# FPGA_Power_Mannager.net
KiCad netlist of a schematic drawn in Altium Designer
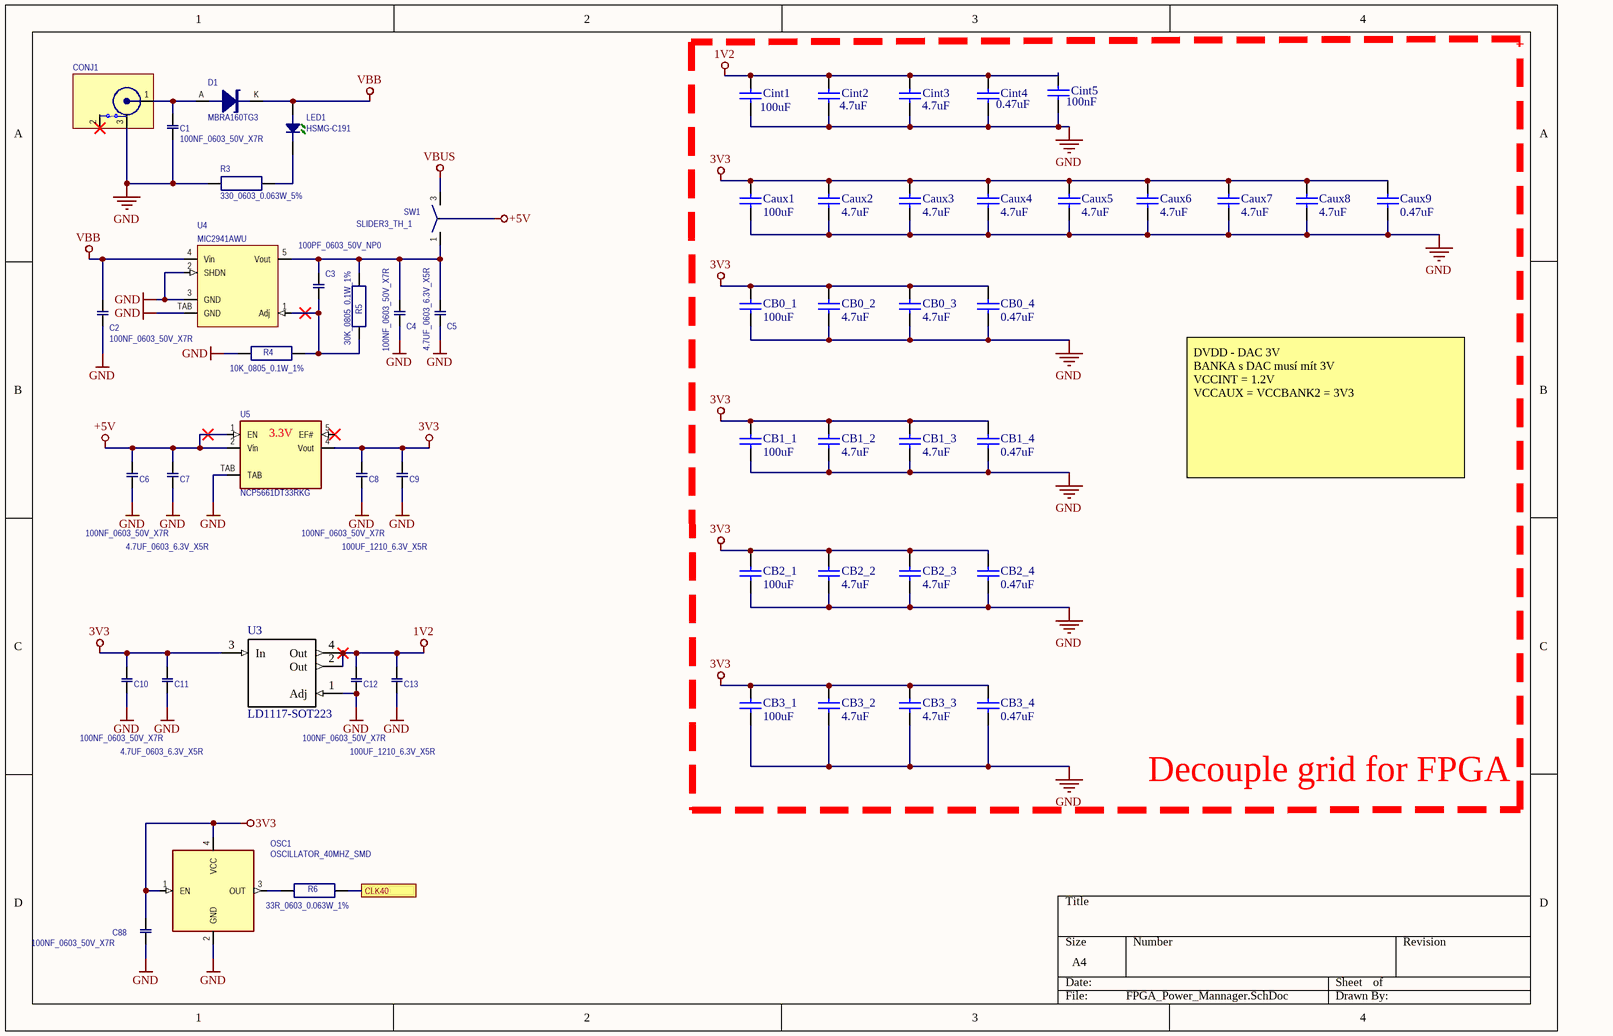
[diagram p0: FPGA_Power_Mannager.SchDoc]

(export (version "E")
  (design (tool "Eeschema 10.0.6"))
  (components
    (comp (ref "C1")
      (value "100NF_0603_50V_X7R")
      (footprint "CAP0603")
      (description "128-8255    Capacitor MLC-X7R_0603_100NF_10%_50V; C0603C104K5RAC; KEMET; RoHS=Yes")
      (libsource (lib "*") (part "100NF_0603_50V_X7R"))
    )
    (comp (ref "C2")
      (value "100NF_0603_50V_X7R")
      (footprint "CAP0603")
      (description "128-8255    Capacitor MLC-X7R_0603_100NF_10%_50V; C0603C104K5RAC; KEMET; RoHS=Yes")
      (libsource (lib "*") (part "100NF_0603_50V_X7R"))
    )
    (comp (ref "C3")
      (value "100PF_0603_50V_NP0")
      (footprint "CAP0603")
      (description "141-4603    Capacitor MLC-NPO_0603_100PF_5%_50V; C0603C101J5GAC; KEMET; RoHS=Yes")
      (libsource (lib "*") (part "100PF_0603_50V_NP0"))
    )
    (comp (ref "C4")
      (value "100NF_0603_50V_X7R")
      (footprint "CAP0603")
      (description "128-8255    Capacitor MLC-X7R_0603_100NF_10%_50V; C0603C104K5RAC; KEMET; RoHS=Yes")
      (libsource (lib "*") (part "100NF_0603_50V_X7R"))
    )
    (comp (ref "C5")
      (value "4.7UF_0603_6.3V_X5R")
      (footprint "CAP0603")
      (description "940-2110    Capacitor MLC-X5R_0603_4.7uF_10%_6.3V; 225520613672; PHYCOMP; RoHS=Yes")
      (libsource (lib "*") (part "4.7UF_0603_6.3V_X5R"))
    )
    (comp (ref "C6")
      (value "100NF_0603_50V_X7R")
      (footprint "CAP0603")
      (description "128-8255    Capacitor MLC-X7R_0603_100NF_10%_50V; C0603C104K5RAC; KEMET; RoHS=Yes")
      (libsource (lib "*") (part "100NF_0603_50V_X7R"))
    )
    (comp (ref "C7")
      (value "4.7UF_0603_6.3V_X5R")
      (footprint "CAP0603")
      (description "940-2110    Capacitor MLC-X5R_0603_4.7uF_10%_6.3V; 225520613672; PHYCOMP; RoHS=Yes")
      (libsource (lib "*") (part "4.7UF_0603_6.3V_X5R"))
    )
    (comp (ref "C8")
      (value "100NF_0603_50V_X7R")
      (footprint "CAP0603")
      (description "128-8255    Capacitor MLC-X7R_0603_100NF_10%_50V; C0603C104K5RAC; KEMET; RoHS=Yes")
      (libsource (lib "*") (part "100NF_0603_50V_X7R"))
    )
    (comp (ref "C9")
      (value "100UF_1210_6.3V_X5R")
      (footprint "CAP1210")
      (description "182-8817    Capacitor CML 100uF_1210_6.3V_X5R_20%; GRM32ER60J107ME20L; MURATA; RoHS=Yes")
      (libsource (lib "*") (part "100UF_1210_6.3V_X5R"))
    )
    (comp (ref "C10")
      (value "100NF_0603_50V_X7R")
      (footprint "CAP0603")
      (description "128-8255    Capacitor MLC-X7R_0603_100NF_10%_50V; C0603C104K5RAC; KEMET; RoHS=Yes")
      (libsource (lib "*") (part "100NF_0603_50V_X7R"))
    )
    (comp (ref "C11")
      (value "4.7UF_0603_6.3V_X5R")
      (footprint "CAP0603")
      (description "940-2110    Capacitor MLC-X5R_0603_4.7uF_10%_6.3V; 225520613672; PHYCOMP; RoHS=Yes")
      (libsource (lib "*") (part "4.7UF_0603_6.3V_X5R"))
    )
    (comp (ref "C12")
      (value "100NF_0603_50V_X7R")
      (footprint "CAP0603")
      (description "128-8255    Capacitor MLC-X7R_0603_100NF_10%_50V; C0603C104K5RAC; KEMET; RoHS=Yes")
      (libsource (lib "*") (part "100NF_0603_50V_X7R"))
    )
    (comp (ref "C13")
      (value "100UF_1210_6.3V_X5R")
      (footprint "CAP1210")
      (description "182-8817    Capacitor CML 100uF_1210_6.3V_X5R_20%; GRM32ER60J107ME20L; MURATA; RoHS=Yes")
      (libsource (lib "*") (part "100UF_1210_6.3V_X5R"))
    )
    (comp (ref "C88")
      (value "100NF_0603_50V_X7R")
      (footprint "CAP0603")
      (description "128-8255    Capacitor MLC-X7R_0603_100NF_10%_50V; C0603C104K5RAC; KEMET; RoHS=Yes")
      (libsource (lib "*") (part "100NF_0603_50V_X7R"))
    )
    (comp (ref "Caux1")
      (value "100uF")
      (footprint "C1206")
      (description "Capacitor (Semiconductor SIM Model)")
      (fields (field (name "Comment") "100UF") (field (name "PUBLISHER") "Altium Limited"))
      (libsource (lib "Miscellaneous Devices") (part "Cap Semi"))
    )
    (comp (ref "Caux2")
      (value "4.7uF")
      (footprint "1608[0603]")
      (description "Capacitor (Semiconductor SIM Model)")
      (fields (field (name "Comment") "4.7UF") (field (name "PUBLISHER") "Altium Limited"))
      (libsource (lib "Miscellaneous Devices") (part "Cap Semi"))
    )
    (comp (ref "Caux3")
      (value "4.7uF")
      (footprint "1608[0603]")
      (description "Capacitor (Semiconductor SIM Model)")
      (fields (field (name "Comment") "4.7UF") (field (name "PUBLISHER") "Altium Limited"))
      (libsource (lib "Miscellaneous Devices") (part "Cap Semi"))
    )
    (comp (ref "Caux4")
      (value "4.7uF")
      (footprint "1608[0603]")
      (description "Capacitor (Semiconductor SIM Model)")
      (fields (field (name "Comment") "4.7UF") (field (name "PUBLISHER") "Altium Limited"))
      (libsource (lib "Miscellaneous Devices") (part "Cap Semi"))
    )
    (comp (ref "Caux5")
      (value "4.7uF")
      (footprint "1608[0603]")
      (description "Capacitor (Semiconductor SIM Model)")
      (fields (field (name "Comment") "4.7UF") (field (name "PUBLISHER") "Altium Limited"))
      (libsource (lib "Miscellaneous Devices") (part "Cap Semi"))
    )
    (comp (ref "Caux6")
      (value "4.7uF")
      (footprint "1608[0603]")
      (description "Capacitor (Semiconductor SIM Model)")
      (fields (field (name "Comment") "4.7UF") (field (name "PUBLISHER") "Altium Limited"))
      (libsource (lib "Miscellaneous Devices") (part "Cap Semi"))
    )
    (comp (ref "Caux7")
      (value "4.7uF")
      (footprint "1608[0603]")
      (description "Capacitor (Semiconductor SIM Model)")
      (fields (field (name "Comment") "4.7UF") (field (name "PUBLISHER") "Altium Limited"))
      (libsource (lib "Miscellaneous Devices") (part "Cap Semi"))
    )
    (comp (ref "Caux8")
      (value "4.7uF")
      (footprint "1608[0603]")
      (description "Capacitor (Semiconductor SIM Model)")
      (fields (field (name "Comment") "4.7UF") (field (name "PUBLISHER") "Altium Limited"))
      (libsource (lib "Miscellaneous Devices") (part "Cap Semi"))
    )
    (comp (ref "Caux9")
      (value "0.47uF")
      (footprint "1608[0603]")
      (description "Capacitor (Semiconductor SIM Model)")
      (fields (field (name "Comment") "470nF") (field (name "PUBLISHER") "Altium Limited"))
      (libsource (lib "Miscellaneous Devices") (part "Cap Semi"))
    )
    (comp (ref "CB0_1")
      (value "100uF")
      (footprint "C1206")
      (description "Capacitor (Semiconductor SIM Model)")
      (fields (field (name "Comment") "100UF") (field (name "PUBLISHER") "Altium Limited"))
      (libsource (lib "Miscellaneous Devices") (part "Cap Semi"))
    )
    (comp (ref "CB0_2")
      (value "4.7uF")
      (footprint "1608[0603]")
      (description "Capacitor (Semiconductor SIM Model)")
      (fields (field (name "Comment") "4.7UF") (field (name "PUBLISHER") "Altium Limited"))
      (libsource (lib "Miscellaneous Devices") (part "Cap Semi"))
    )
    (comp (ref "CB0_3")
      (value "4.7uF")
      (footprint "1608[0603]")
      (description "Capacitor (Semiconductor SIM Model)")
      (fields (field (name "Comment") "4.7UF") (field (name "PUBLISHER") "Altium Limited"))
      (libsource (lib "Miscellaneous Devices") (part "Cap Semi"))
    )
    (comp (ref "CB0_4")
      (value "0.47uF")
      (footprint "1608[0603]")
      (description "Capacitor (Semiconductor SIM Model)")
      (fields (field (name "Comment") "470nF") (field (name "PUBLISHER") "Altium Limited"))
      (libsource (lib "Miscellaneous Devices") (part "Cap Semi"))
    )
    (comp (ref "CB1_1")
      (value "100uF")
      (footprint "C1206")
      (description "Capacitor (Semiconductor SIM Model)")
      (fields (field (name "Comment") "100UF") (field (name "PUBLISHER") "Altium Limited"))
      (libsource (lib "Miscellaneous Devices") (part "Cap Semi"))
    )
    (comp (ref "CB1_2")
      (value "4.7uF")
      (footprint "1608[0603]")
      (description "Capacitor (Semiconductor SIM Model)")
      (fields (field (name "Comment") "4.7UF") (field (name "PUBLISHER") "Altium Limited"))
      (libsource (lib "Miscellaneous Devices") (part "Cap Semi"))
    )
    (comp (ref "CB1_3")
      (value "4.7uF")
      (footprint "1608[0603]")
      (description "Capacitor (Semiconductor SIM Model)")
      (fields (field (name "Comment") "4.7UF") (field (name "PUBLISHER") "Altium Limited"))
      (libsource (lib "Miscellaneous Devices") (part "Cap Semi"))
    )
    (comp (ref "CB1_4")
      (value "0.47uF")
      (footprint "1608[0603]")
      (description "Capacitor (Semiconductor SIM Model)")
      (fields (field (name "Comment") "470nF") (field (name "PUBLISHER") "Altium Limited"))
      (libsource (lib "Miscellaneous Devices") (part "Cap Semi"))
    )
    (comp (ref "CB2_1")
      (value "100uF")
      (footprint "C1206")
      (description "Capacitor (Semiconductor SIM Model)")
      (fields (field (name "Comment") "100UF") (field (name "PUBLISHER") "Altium Limited"))
      (libsource (lib "Miscellaneous Devices") (part "Cap Semi"))
    )
    (comp (ref "CB2_2")
      (value "4.7uF")
      (footprint "1608[0603]")
      (description "Capacitor (Semiconductor SIM Model)")
      (fields (field (name "Comment") "4.7UF") (field (name "PUBLISHER") "Altium Limited"))
      (libsource (lib "Miscellaneous Devices") (part "Cap Semi"))
    )
    (comp (ref "CB2_3")
      (value "4.7uF")
      (footprint "1608[0603]")
      (description "Capacitor (Semiconductor SIM Model)")
      (fields (field (name "Comment") "4.7UF") (field (name "PUBLISHER") "Altium Limited"))
      (libsource (lib "Miscellaneous Devices") (part "Cap Semi"))
    )
    (comp (ref "CB2_4")
      (value "0.47uF")
      (footprint "1608[0603]")
      (description "Capacitor (Semiconductor SIM Model)")
      (fields (field (name "Comment") "470nF") (field (name "PUBLISHER") "Altium Limited"))
      (libsource (lib "Miscellaneous Devices") (part "Cap Semi"))
    )
    (comp (ref "CB3_1")
      (value "100uF")
      (footprint "C1206")
      (description "Capacitor (Semiconductor SIM Model)")
      (fields (field (name "Comment") "100UF") (field (name "PUBLISHER") "Altium Limited"))
      (libsource (lib "Miscellaneous Devices") (part "Cap Semi"))
    )
    (comp (ref "CB3_2")
      (value "4.7uF")
      (footprint "1608[0603]")
      (description "Capacitor (Semiconductor SIM Model)")
      (fields (field (name "Comment") "4.7UF") (field (name "PUBLISHER") "Altium Limited"))
      (libsource (lib "Miscellaneous Devices") (part "Cap Semi"))
    )
    (comp (ref "CB3_3")
      (value "4.7uF")
      (footprint "1608[0603]")
      (description "Capacitor (Semiconductor SIM Model)")
      (fields (field (name "Comment") "4.7UF") (field (name "PUBLISHER") "Altium Limited"))
      (libsource (lib "Miscellaneous Devices") (part "Cap Semi"))
    )
    (comp (ref "CB3_4")
      (value "0.47uF")
      (footprint "1608[0603]")
      (description "Capacitor (Semiconductor SIM Model)")
      (fields (field (name "Comment") "470nF") (field (name "PUBLISHER") "Altium Limited"))
      (libsource (lib "Miscellaneous Devices") (part "Cap Semi"))
    )
    (comp (ref "Cint1")
      (value "100uF")
      (footprint "C1206")
      (description "Capacitor (Semiconductor SIM Model)")
      (fields (field (name "Comment") "100UF") (field (name "PUBLISHER") "Altium Limited"))
      (libsource (lib "Miscellaneous Devices") (part "Cap Semi"))
    )
    (comp (ref "Cint2")
      (value "4.7uF")
      (footprint "1608[0603]")
      (description "Capacitor (Semiconductor SIM Model)")
      (fields (field (name "Comment") "4.7UF") (field (name "PUBLISHER") "Altium Limited"))
      (libsource (lib "Miscellaneous Devices") (part "Cap Semi"))
    )
    (comp (ref "Cint3")
      (value "4.7uF")
      (footprint "1608[0603]")
      (description "Capacitor (Semiconductor SIM Model)")
      (fields (field (name "Comment") "4.7UF") (field (name "PUBLISHER") "Altium Limited"))
      (libsource (lib "Miscellaneous Devices") (part "Cap Semi"))
    )
    (comp (ref "Cint4")
      (value "0.47uF")
      (footprint "1608[0603]")
      (description "Capacitor (Semiconductor SIM Model)")
      (fields (field (name "Comment") "470nF") (field (name "PUBLISHER") "Altium Limited"))
      (libsource (lib "Miscellaneous Devices") (part "Cap Semi"))
    )
    (comp (ref "Cint5")
      (value "100nF")
      (footprint "1608[0603]")
      (description "Capacitor (Semiconductor SIM Model)")
      (fields (field (name "PUBLISHER") "Altium Limited"))
      (libsource (lib "Miscellaneous Devices") (part "Cap Semi"))
    )
    (comp (ref "CONJ1")
      (value "CON_POWER_DC10A_CLIFF")
      (footprint "CON_POWER_DC10A_CLIFF")
      (libsource (lib "ONEMULA_V2") (part "CON_POWER_DC10A_CLIFF"))
    )
    (comp (ref "D1")
      (value "MBRA160TG3")
      (footprint "SMA_KA")
      (description "143-1076    DIODE SCHOTTKY 60V/1A; MBRA160TG3; SMA; ONSEMI; RoHS=Yes")
      (libsource (lib "ONEMULA_V2") (part "MBRA160TG3"))
    )
    (comp (ref "LED1")
      (value "HSMG-C191")
      (footprint "D0603")
      (description "855-4617    LED DIODE GREEN 20mA, 0603; HSMG-C191; AVAGO TECHNOLOGIES; RoHS=Yes")
      (libsource (lib "ONEMULA_V2") (part "HSMG-C191"))
    )
    (comp (ref "OSC1")
      (value "OSCILLATOR_40MHZ_SMD")
      (footprint "CFPS-73")
      (libsource (lib "ONEMULA_V1_ALLPATCHES") (part "OSCILLATOR_40MHZ_SMD"))
    )
    (comp (ref "R3")
      (value "330_0603_0.063W_5%")
      (footprint "R0603")
      (description "923-3385    RESISTOR MF_0603_1.0KR_0.063W_5%_50V; 232270260102; PHYCOMP; RoHS=Yes")
      (libsource (lib "ONEMULA_V2") (part "1.0K_0603_0.063W_5%"))
    )
    (comp (ref "R4")
      (value "10K_0805_0.1W_1%")
      (footprint "R0805")
      (libsource (lib "*") (part "10K_0805_0.1W_1%"))
    )
    (comp (ref "R5")
      (value "30K_0805_0.1W_1%")
      (footprint "R0805")
      (libsource (lib "*") (part "30K_0805_0.1W_1%"))
    )
    (comp (ref "R6")
      (value "33R_0603_0.063W_1%")
      (footprint "R0603")
      (description "933-1050    RESISTOR MF_0603_33R_0.063W_1%_50V; MC_0.063W_0603_1%_33R; MULTICOMP; RoHS=Yes")
      (libsource (lib "*") (part "33R_0603_0.063W_1%"))
    )
    (comp (ref "SW1")
      (value "SLIDER3_TH_1")
      (footprint "X3APH-SLIDER")
      (description "674-345     SWITCH SLIDE SPDT VERT; 09-03290-01; EAO; RoHS=Yes")
      (libsource (lib "*") (part "SLIDER3_TH_1"))
    )
    (comp (ref "U3")
      (value "LD1117-SOT223")
      (footprint "SOT223")
      (libsource (lib "vh_altium_library") (part "LD1117-SOT223"))
    )
    (comp (ref "U4")
      (value "MIC2941AWU")
      (footprint "TO263_5")
      (description "155-6739    VOLTAGE REGULATOR, ADJ/1,5A, MIC2941AWU; MICREL; RoHS=Yes")
      (libsource (lib "*") (part "MIC2941AWU"))
    )
    (comp (ref "U5")
      (value "NCP5661DT33RKG")
      (footprint "DPAK5")
      (description "ONSEMI      VOLTAGE REGULATOR NCP5661DT33RKG, LINEAR, LDO, 3.3V/1A, DPAK5; ONSEMI; RoHS=Yes")
      (libsource (lib "ONEMULA_V1_ALLPATCHES") (part "NCP5661DT33RKG"))
    )
  )
  (nets
    (net (code "1") (name "+5V") (class "Default")
      (node (ref "C6") (pin "1") (pinfunction "1_1") (pintype "passive"))
      (node (ref "C7") (pin "1") (pinfunction "1_1") (pintype "passive"))
      (node (ref "SW1") (pin "2") (pinfunction "2_2") (pintype "passive"))
      (node (ref "U5") (pin "1") (pinfunction "EN_1") (pintype "input"))
      (node (ref "U5") (pin "2") (pinfunction "Vin_2") (pintype "power_in"))
    )
    (net (code "2") (name "/CLK40") (class "Default")
      (node (ref "R6") (pin "2") (pinfunction "2_2") (pintype "passive"))
    )
    (net (code "3") (name "1V2") (class "Default")
      (node (ref "C12") (pin "1") (pinfunction "1_1") (pintype "passive"))
      (node (ref "C13") (pin "1") (pinfunction "1_1") (pintype "passive"))
      (node (ref "Cint1") (pin "2") (pinfunction "2_2") (pintype "passive"))
      (node (ref "Cint2") (pin "2") (pinfunction "2_2") (pintype "passive"))
      (node (ref "Cint3") (pin "2") (pinfunction "2_2") (pintype "passive"))
      (node (ref "Cint4") (pin "2") (pinfunction "2_2") (pintype "passive"))
      (node (ref "Cint5") (pin "2") (pinfunction "2_2") (pintype "passive"))
      (node (ref "U3") (pin "2") (pinfunction "Out_2") (pintype "output"))
      (node (ref "U3") (pin "4") (pinfunction "Out_4") (pintype "output"))
    )
    (net (code "4") (name "3V3") (class "Default")
      (node (ref "C10") (pin "1") (pinfunction "1_1") (pintype "passive"))
      (node (ref "C11") (pin "1") (pinfunction "1_1") (pintype "passive"))
      (node (ref "C8") (pin "1") (pinfunction "1_1") (pintype "passive"))
      (node (ref "C88") (pin "2") (pinfunction "2_2") (pintype "passive"))
      (node (ref "C9") (pin "1") (pinfunction "1_1") (pintype "passive"))
      (node (ref "CB0_1") (pin "2") (pinfunction "2_2") (pintype "passive"))
      (node (ref "CB0_2") (pin "2") (pinfunction "2_2") (pintype "passive"))
      (node (ref "CB0_3") (pin "2") (pinfunction "2_2") (pintype "passive"))
      (node (ref "CB0_4") (pin "2") (pinfunction "2_2") (pintype "passive"))
      (node (ref "CB1_1") (pin "2") (pinfunction "2_2") (pintype "passive"))
      (node (ref "CB1_2") (pin "2") (pinfunction "2_2") (pintype "passive"))
      (node (ref "CB1_3") (pin "2") (pinfunction "2_2") (pintype "passive"))
      (node (ref "CB1_4") (pin "2") (pinfunction "2_2") (pintype "passive"))
      (node (ref "CB2_1") (pin "2") (pinfunction "2_2") (pintype "passive"))
      (node (ref "CB2_2") (pin "2") (pinfunction "2_2") (pintype "passive"))
      (node (ref "CB2_3") (pin "2") (pinfunction "2_2") (pintype "passive"))
      (node (ref "CB2_4") (pin "2") (pinfunction "2_2") (pintype "passive"))
      (node (ref "CB3_1") (pin "2") (pinfunction "2_2") (pintype "passive"))
      (node (ref "CB3_2") (pin "2") (pinfunction "2_2") (pintype "passive"))
      (node (ref "CB3_3") (pin "2") (pinfunction "2_2") (pintype "passive"))
      (node (ref "CB3_4") (pin "2") (pinfunction "2_2") (pintype "passive"))
      (node (ref "Caux1") (pin "2") (pinfunction "2_2") (pintype "passive"))
      (node (ref "Caux2") (pin "2") (pinfunction "2_2") (pintype "passive"))
      (node (ref "Caux3") (pin "2") (pinfunction "2_2") (pintype "passive"))
      (node (ref "Caux4") (pin "2") (pinfunction "2_2") (pintype "passive"))
      (node (ref "Caux5") (pin "2") (pinfunction "2_2") (pintype "passive"))
      (node (ref "Caux6") (pin "2") (pinfunction "2_2") (pintype "passive"))
      (node (ref "Caux7") (pin "2") (pinfunction "2_2") (pintype "passive"))
      (node (ref "Caux8") (pin "2") (pinfunction "2_2") (pintype "passive"))
      (node (ref "Caux9") (pin "2") (pinfunction "2_2") (pintype "passive"))
      (node (ref "OSC1") (pin "1") (pinfunction "EN_1") (pintype "input"))
      (node (ref "OSC1") (pin "4") (pinfunction "VCC_4") (pintype "power_in"))
      (node (ref "U3") (pin "3") (pinfunction "In_3") (pintype "input"))
      (node (ref "U5") (pin "4") (pinfunction "Vout_4") (pintype "power_in"))
    )
    (net (code "5") (name "GND") (class "Default")
      (node (ref "C1") (pin "1") (pinfunction "1_1") (pintype "passive"))
      (node (ref "C10") (pin "2") (pinfunction "2_2") (pintype "passive"))
      (node (ref "C11") (pin "2") (pinfunction "2_2") (pintype "passive"))
      (node (ref "C12") (pin "2") (pinfunction "2_2") (pintype "passive"))
      (node (ref "C13") (pin "2") (pinfunction "2_2") (pintype "passive"))
      (node (ref "C2") (pin "1") (pinfunction "1_1") (pintype "passive"))
      (node (ref "C4") (pin "2") (pinfunction "2_2") (pintype "passive"))
      (node (ref "C5") (pin "2") (pinfunction "2_2") (pintype "passive"))
      (node (ref "C6") (pin "2") (pinfunction "2_2") (pintype "passive"))
      (node (ref "C7") (pin "2") (pinfunction "2_2") (pintype "passive"))
      (node (ref "C8") (pin "2") (pinfunction "2_2") (pintype "passive"))
      (node (ref "C88") (pin "1") (pinfunction "1_1") (pintype "passive"))
      (node (ref "C9") (pin "2") (pinfunction "2_2") (pintype "passive"))
      (node (ref "CB0_1") (pin "1") (pinfunction "1_1") (pintype "passive"))
      (node (ref "CB0_2") (pin "1") (pinfunction "1_1") (pintype "passive"))
      (node (ref "CB0_3") (pin "1") (pinfunction "1_1") (pintype "passive"))
      (node (ref "CB0_4") (pin "1") (pinfunction "1_1") (pintype "passive"))
      (node (ref "CB1_1") (pin "1") (pinfunction "1_1") (pintype "passive"))
      (node (ref "CB1_2") (pin "1") (pinfunction "1_1") (pintype "passive"))
      (node (ref "CB1_3") (pin "1") (pinfunction "1_1") (pintype "passive"))
      (node (ref "CB1_4") (pin "1") (pinfunction "1_1") (pintype "passive"))
      (node (ref "CB2_1") (pin "1") (pinfunction "1_1") (pintype "passive"))
      (node (ref "CB2_2") (pin "1") (pinfunction "1_1") (pintype "passive"))
      (node (ref "CB2_3") (pin "1") (pinfunction "1_1") (pintype "passive"))
      (node (ref "CB2_4") (pin "1") (pinfunction "1_1") (pintype "passive"))
      (node (ref "CB3_1") (pin "1") (pinfunction "1_1") (pintype "passive"))
      (node (ref "CB3_2") (pin "1") (pinfunction "1_1") (pintype "passive"))
      (node (ref "CB3_3") (pin "1") (pinfunction "1_1") (pintype "passive"))
      (node (ref "CB3_4") (pin "1") (pinfunction "1_1") (pintype "passive"))
      (node (ref "CONJ1") (pin "3") (pinfunction "3_3") (pintype "passive"))
      (node (ref "Caux1") (pin "1") (pinfunction "1_1") (pintype "passive"))
      (node (ref "Caux2") (pin "1") (pinfunction "1_1") (pintype "passive"))
      (node (ref "Caux3") (pin "1") (pinfunction "1_1") (pintype "passive"))
      (node (ref "Caux4") (pin "1") (pinfunction "1_1") (pintype "passive"))
      (node (ref "Caux5") (pin "1") (pinfunction "1_1") (pintype "passive"))
      (node (ref "Caux6") (pin "1") (pinfunction "1_1") (pintype "passive"))
      (node (ref "Caux7") (pin "1") (pinfunction "1_1") (pintype "passive"))
      (node (ref "Caux8") (pin "1") (pinfunction "1_1") (pintype "passive"))
      (node (ref "Caux9") (pin "1") (pinfunction "1_1") (pintype "passive"))
      (node (ref "Cint1") (pin "1") (pinfunction "1_1") (pintype "passive"))
      (node (ref "Cint2") (pin "1") (pinfunction "1_1") (pintype "passive"))
      (node (ref "Cint3") (pin "1") (pinfunction "1_1") (pintype "passive"))
      (node (ref "Cint4") (pin "1") (pinfunction "1_1") (pintype "passive"))
      (node (ref "Cint5") (pin "1") (pinfunction "1_1") (pintype "passive"))
      (node (ref "OSC1") (pin "2") (pinfunction "GND_2") (pintype "power_in"))
      (node (ref "R3") (pin "1") (pinfunction "1_1") (pintype "passive"))
      (node (ref "R4") (pin "1") (pinfunction "1_1") (pintype "passive"))
      (node (ref "U3") (pin "1") (pinfunction "Adj_1") (pintype "input"))
      (node (ref "U4") (pin "2") (pinfunction "SHDN_2") (pintype "input"))
      (node (ref "U4") (pin "3") (pinfunction "GND_3") (pintype "power_in"))
      (node (ref "U4") (pin "TAB") (pinfunction "GND_TAB") (pintype "power_in"))
      (node (ref "U5") (pin "TAB") (pinfunction "TAB_TAB") (pintype "passive"))
    )
    (net (code "6") (name "Net-(D1-ANODE)") (class "Default")
      (node (ref "C1") (pin "2") (pinfunction "2_2") (pintype "passive"))
      (node (ref "CONJ1") (pin "1") (pinfunction "1_1") (pintype "passive"))
      (node (ref "D1") (pin "A") (pinfunction "ANODE_A") (pintype "passive"))
    )
    (net (code "7") (name "Net-(LED1-PadK)") (class "Default")
      (node (ref "LED1") (pin "K") (pinfunction "K_K") (pintype "passive"))
      (node (ref "R3") (pin "2") (pinfunction "2_2") (pintype "passive"))
    )
    (net (code "8") (name "Net-(OSC1-OUT)") (class "Default")
      (node (ref "OSC1") (pin "3") (pinfunction "OUT_3") (pintype "output"))
      (node (ref "R6") (pin "1") (pinfunction "1_1") (pintype "passive"))
    )
    (net (code "9") (name "Net-(U4-Adj)") (class "Default")
      (node (ref "C3") (pin "1") (pinfunction "1_1") (pintype "passive"))
      (node (ref "R4") (pin "2") (pinfunction "2_2") (pintype "passive"))
      (node (ref "R5") (pin "2") (pinfunction "2_2") (pintype "passive"))
      (node (ref "U4") (pin "1") (pinfunction "Adj_1") (pintype "input"))
    )
    (net (code "10") (name "Net-(U4-Vout)") (class "Default")
      (node (ref "C3") (pin "2") (pinfunction "2_2") (pintype "passive"))
      (node (ref "C4") (pin "1") (pinfunction "1_1") (pintype "passive"))
      (node (ref "C5") (pin "1") (pinfunction "1_1") (pintype "passive"))
      (node (ref "R5") (pin "1") (pinfunction "1_1") (pintype "passive"))
      (node (ref "SW1") (pin "1") (pinfunction "1_1") (pintype "passive"))
      (node (ref "U4") (pin "5") (pinfunction "Vout_5") (pintype "power_in"))
    )
    (net (code "11") (name "VBB") (class "Default")
      (node (ref "C2") (pin "2") (pinfunction "2_2") (pintype "passive"))
      (node (ref "D1") (pin "K") (pinfunction "CATHODE_K") (pintype "passive"))
      (node (ref "LED1") (pin "A") (pinfunction "A_A") (pintype "passive"))
      (node (ref "U4") (pin "4") (pinfunction "Vin_4") (pintype "power_in"))
    )
    (net (code "12") (name "VBUS") (class "Default")
      (node (ref "SW1") (pin "3") (pinfunction "3_3") (pintype "passive"))
    )
    (net (code "13") (name "unconnected-(CONJ1-Pad2)") (class "Default")
      (node (ref "CONJ1") (pin "2") (pinfunction "2_2") (pintype "passive+no_connect"))
    )
    (net (code "14") (name "unconnected-(U5-EF#-Pad5)") (class "Default")
      (node (ref "U5") (pin "5") (pinfunction "EF#_5") (pintype "input+no_connect"))
    )
  )
)
